# SCH_HC_Business_Card_2023-06-01.net
KiCad netlist of a schematic drawn in EasyEDA
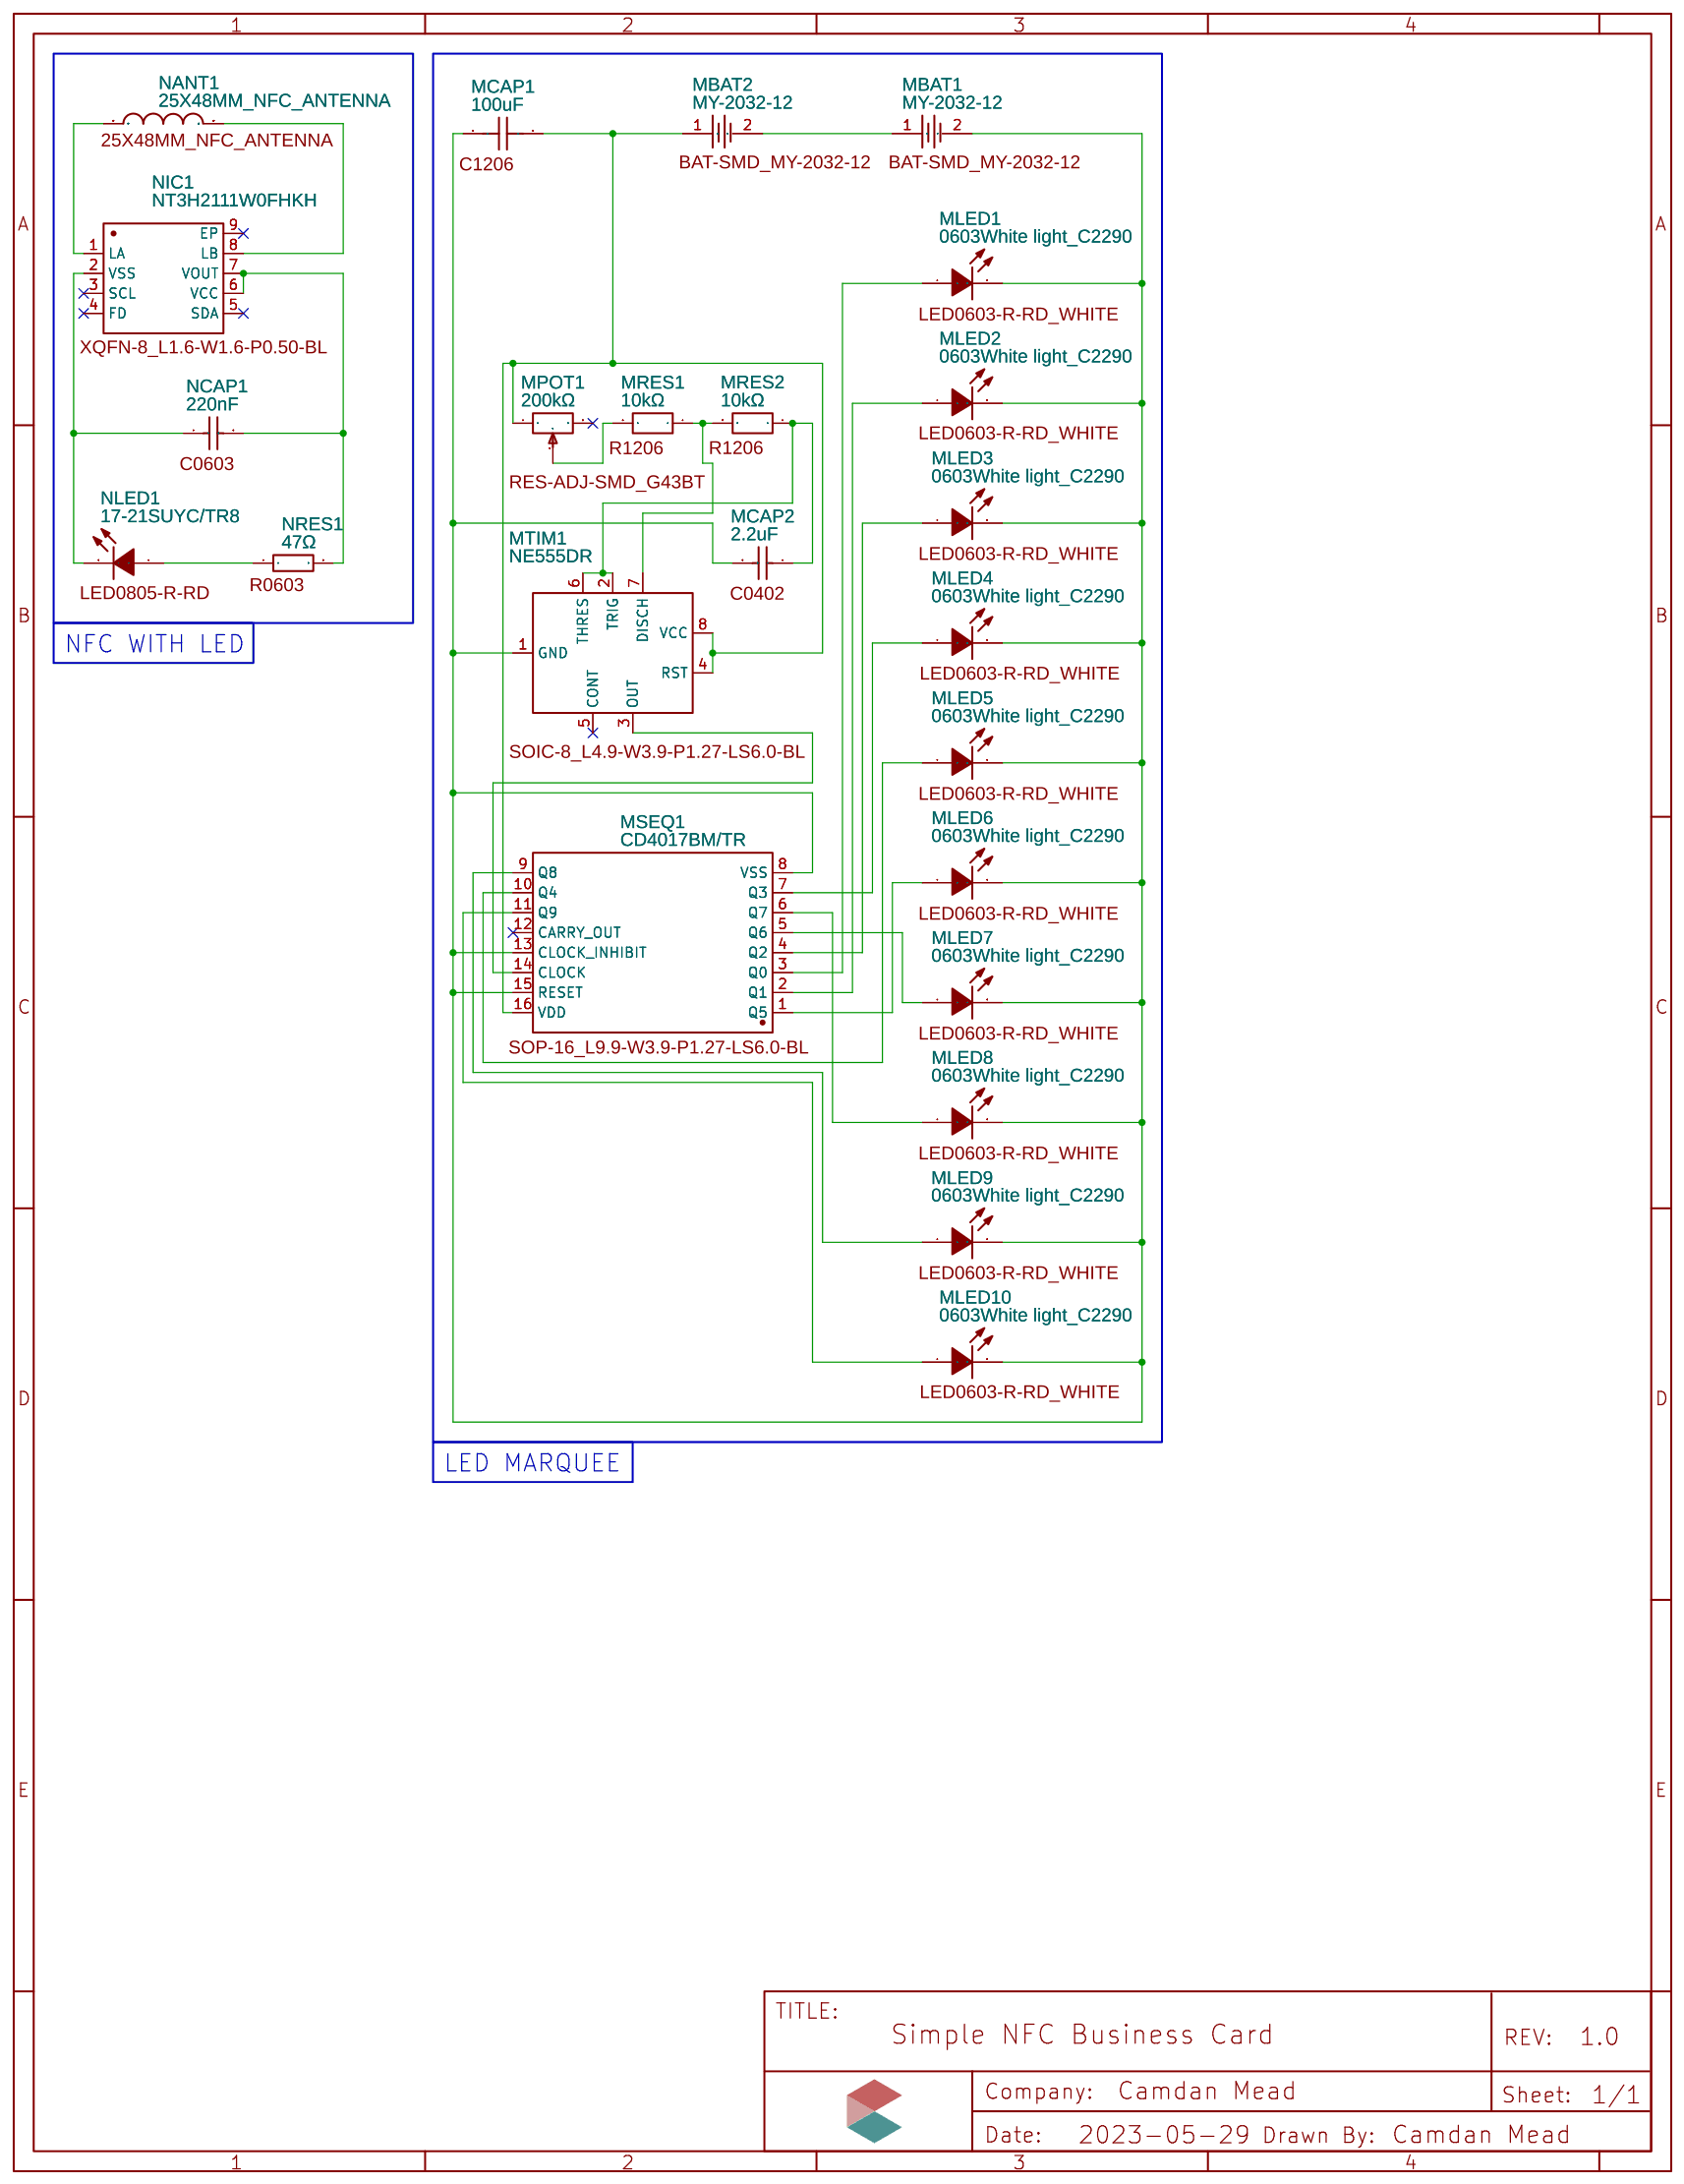
[diagram p0: schematic sheet]

(export (version "E")
  (design (tool "Eeschema 10.0.6"))
  (components
    (comp (ref "MBAT1")
      (value "MY-2032-12")
      (fields (field (name "BOM_Supplier Part") "C964833"))
      (libsource (lib "") (part "MY-2032-12"))
    )
    (comp (ref "MBAT2")
      (value "MY-2032-12")
      (fields (field (name "BOM_Supplier Part") "C964833"))
      (libsource (lib "") (part "MY-2032-12"))
    )
    (comp (ref "MCAP1")
      (value "100uF")
      (fields
        (field (name "BOM_Manufacturer Part") "JMK316ABJ107ML-T")
        (field (name "BOM_Supplier Part") "C268006")
      )
      (libsource (lib "") (part "JMK316ABJ107ML-T"))
    )
    (comp (ref "MCAP2")
      (value "2.2uF")
      (fields
        (field (name "BOM_Manufacturer Part") "GRM155R60J225ME15D")
        (field (name "BOM_Supplier Part") "C76993")
      )
      (libsource (lib "") (part "GRM155R60J225ME15D"))
    )
    (comp (ref "MLED1")
      (value "0603White light_C2290")
      (fields (field (name "BOM_Manufacturer Part") "KT-0603白灯") (field (name "BOM_Supplier Part") "C2290"))
      (libsource (lib "") (part "0603White light_C2290_1"))
    )
    (comp (ref "MLED2")
      (value "0603White light_C2290")
      (fields (field (name "BOM_Manufacturer Part") "KT-0603白灯") (field (name "BOM_Supplier Part") "C2290"))
      (libsource (lib "") (part "0603White light_C2290"))
    )
    (comp (ref "MLED3")
      (value "0603White light_C2290")
      (fields (field (name "BOM_Manufacturer Part") "KT-0603白灯") (field (name "BOM_Supplier Part") "C2290"))
      (libsource (lib "") (part "0603White light_C2290_4"))
    )
    (comp (ref "MLED4")
      (value "0603White light_C2290")
      (fields (field (name "BOM_Manufacturer Part") "KT-0603白灯") (field (name "BOM_Supplier Part") "C2290"))
      (libsource (lib "") (part "0603White light_C2290_2"))
    )
    (comp (ref "MLED5")
      (value "0603White light_C2290")
      (fields (field (name "BOM_Manufacturer Part") "KT-0603白灯") (field (name "BOM_Supplier Part") "C2290"))
      (libsource (lib "") (part "0603White light_C2290_1"))
    )
    (comp (ref "MLED6")
      (value "0603White light_C2290")
      (fields (field (name "BOM_Manufacturer Part") "KT-0603白灯") (field (name "BOM_Supplier Part") "C2290"))
      (libsource (lib "") (part "0603White light_C2290_1"))
    )
    (comp (ref "MLED7")
      (value "0603White light_C2290")
      (fields (field (name "BOM_Manufacturer Part") "KT-0603白灯") (field (name "BOM_Supplier Part") "C2290"))
      (libsource (lib "") (part "0603White light_C2290_1"))
    )
    (comp (ref "MLED8")
      (value "0603White light_C2290")
      (fields (field (name "BOM_Manufacturer Part") "KT-0603白灯") (field (name "BOM_Supplier Part") "C2290"))
      (libsource (lib "") (part "0603White light_C2290_1"))
    )
    (comp (ref "MLED9")
      (value "0603White light_C2290")
      (fields (field (name "BOM_Manufacturer Part") "KT-0603白灯") (field (name "BOM_Supplier Part") "C2290"))
      (libsource (lib "") (part "0603White light_C2290_4"))
    )
    (comp (ref "MLED10")
      (value "0603White light_C2290")
      (fields (field (name "BOM_Manufacturer Part") "KT-0603白灯") (field (name "BOM_Supplier Part") "C2290"))
      (libsource (lib "") (part "0603White light_C2290_3"))
    )
    (comp (ref "MPOT1")
      (value "200kΩ")
      (fields
        (field (name "BOM_Manufacturer Part") "G43BT-B204")
        (field (name "BOM_Supplier Part") "C128150")
      )
      (libsource (lib "") (part "G43BT-B204"))
    )
    (comp (ref "MRES1")
      (value "10kΩ")
      (fields
        (field (name "BOM_Manufacturer Part") "CR1206J10K0P05Z")
        (field (name "BOM_Supplier Part") "C881379")
      )
      (libsource (lib "") (part "CR1206J10K0P05Z_1"))
    )
    (comp (ref "MRES2")
      (value "10kΩ")
      (fields
        (field (name "BOM_Manufacturer Part") "CR1206J10K0P05Z")
        (field (name "BOM_Supplier Part") "C881379")
      )
      (libsource (lib "") (part "CR1206J10K0P05Z"))
    )
    (comp (ref "MSEQ1")
      (value "CD4017BM/TR")
      (fields (field (name "BOM_Supplier Part") "C356694"))
      (libsource (lib "") (part "CD4017BM/TR"))
    )
    (comp (ref "MTIM1")
      (value "NE555DR")
      (fields (field (name "BOM_Supplier Part") "C7593"))
      (libsource (lib "") (part "NE555DR"))
    )
    (comp (ref "NANT1") (value "25X48MM_NFC_ANTENNA") (libsource (lib "") (part "25X48MM_NFC_ANTENNA")))
    (comp (ref "NCAP1")
      (value "220nF")
      (fields
        (field (name "BOM_Manufacturer Part") "CL10B224KA8NNNC")
        (field (name "BOM_Supplier Part") "C21120")
      )
      (libsource (lib "") (part "CL10B224KA8NNNC"))
    )
    (comp (ref "NIC1")
      (value "NT3H2111W0FHKH")
      (fields (field (name "BOM_Supplier Part") "C710403"))
      (libsource (lib "") (part "NT3H2111W0FHKH"))
    )
    (comp (ref "NLED1")
      (value "17-21SUYC/TR8")
      (fields (field (name "BOM_Manufacturer Part") "KT-0805黄灯") (field (name "BOM_Supplier Part") "C2296"))
      (libsource (lib "") (part "17-21SUYC/TR8"))
    )
    (comp (ref "NRES1")
      (value "47Ω")
      (fields
        (field (name "BOM_Manufacturer Part") "0603WAF470JT5E")
        (field (name "BOM_Supplier Part") "C23182")
      )
      (libsource (lib "") (part "0603WAF470JT5E"))
    )
  )
  (nets
    (net (code "1") (name "Net-(MBAT1-Pad1)") (class "Default")
      (node (ref "MBAT1") (pin "1") (pinfunction "1_1") (pintype "input"))
      (node (ref "MBAT2") (pin "2") (pinfunction "2_2") (pintype "input"))
    )
    (net (code "2") (name "Net-(MLED1-A)") (class "Default")
      (node (ref "MLED1") (pin "1") (pinfunction "A_1") (pintype "unspecified"))
      (node (ref "MSEQ1") (pin "3") (pinfunction "Q0_3") (pintype "unspecified"))
    )
    (net (code "3") (name "Net-(MLED1-K)") (class "Default")
      (node (ref "MBAT1") (pin "2") (pinfunction "2_2") (pintype "input"))
      (node (ref "MCAP1") (pin "2") (pinfunction "2_2") (pintype "unspecified"))
      (node (ref "MCAP2") (pin "2") (pinfunction "2_2") (pintype "input"))
      (node (ref "MLED1") (pin "2") (pinfunction "K_2") (pintype "unspecified"))
      (node (ref "MLED10") (pin "2") (pinfunction "K_2") (pintype "unspecified"))
      (node (ref "MLED2") (pin "2") (pinfunction "K_2") (pintype "unspecified"))
      (node (ref "MLED3") (pin "2") (pinfunction "K_2") (pintype "unspecified"))
      (node (ref "MLED4") (pin "2") (pinfunction "K_2") (pintype "unspecified"))
      (node (ref "MLED5") (pin "2") (pinfunction "K_2") (pintype "unspecified"))
      (node (ref "MLED6") (pin "2") (pinfunction "K_2") (pintype "unspecified"))
      (node (ref "MLED7") (pin "2") (pinfunction "K_2") (pintype "unspecified"))
      (node (ref "MLED8") (pin "2") (pinfunction "K_2") (pintype "unspecified"))
      (node (ref "MLED9") (pin "2") (pinfunction "K_2") (pintype "unspecified"))
      (node (ref "MSEQ1") (pin "13") (pinfunction "CLOCK_INHIBIT_13") (pintype "unspecified"))
      (node (ref "MSEQ1") (pin "15") (pinfunction "RESET_15") (pintype "unspecified"))
      (node (ref "MSEQ1") (pin "8") (pinfunction "VSS_8") (pintype "unspecified"))
      (node (ref "MTIM1") (pin "1") (pinfunction "GND_1") (pintype "unspecified"))
    )
    (net (code "4") (name "Net-(MLED2-A)") (class "Default")
      (node (ref "MLED2") (pin "1") (pinfunction "A_1") (pintype "unspecified"))
      (node (ref "MSEQ1") (pin "2") (pinfunction "Q1_2") (pintype "unspecified"))
    )
    (net (code "5") (name "Net-(MLED3-A)") (class "Default")
      (node (ref "MLED3") (pin "1") (pinfunction "A_1") (pintype "unspecified"))
      (node (ref "MSEQ1") (pin "4") (pinfunction "Q2_4") (pintype "unspecified"))
    )
    (net (code "6") (name "Net-(MLED4-A)") (class "Default")
      (node (ref "MLED4") (pin "1") (pinfunction "A_1") (pintype "unspecified"))
      (node (ref "MSEQ1") (pin "7") (pinfunction "Q3_7") (pintype "unspecified"))
    )
    (net (code "7") (name "Net-(MLED5-A)") (class "Default")
      (node (ref "MLED5") (pin "1") (pinfunction "A_1") (pintype "unspecified"))
      (node (ref "MSEQ1") (pin "10") (pinfunction "Q4_10") (pintype "unspecified"))
    )
    (net (code "8") (name "Net-(MLED6-A)") (class "Default")
      (node (ref "MLED6") (pin "1") (pinfunction "A_1") (pintype "unspecified"))
      (node (ref "MSEQ1") (pin "1") (pinfunction "Q5_1") (pintype "unspecified"))
    )
    (net (code "9") (name "Net-(MLED7-A)") (class "Default")
      (node (ref "MLED7") (pin "1") (pinfunction "A_1") (pintype "unspecified"))
      (node (ref "MSEQ1") (pin "5") (pinfunction "Q6_5") (pintype "unspecified"))
    )
    (net (code "10") (name "Net-(MLED8-A)") (class "Default")
      (node (ref "MLED8") (pin "1") (pinfunction "A_1") (pintype "unspecified"))
      (node (ref "MSEQ1") (pin "6") (pinfunction "Q7_6") (pintype "unspecified"))
    )
    (net (code "11") (name "Net-(MLED9-A)") (class "Default")
      (node (ref "MLED9") (pin "1") (pinfunction "A_1") (pintype "unspecified"))
      (node (ref "MSEQ1") (pin "9") (pinfunction "Q8_9") (pintype "unspecified"))
    )
    (net (code "12") (name "Net-(MLED10-A)") (class "Default")
      (node (ref "MLED10") (pin "1") (pinfunction "A_1") (pintype "unspecified"))
      (node (ref "MSEQ1") (pin "11") (pinfunction "Q9_11") (pintype "unspecified"))
    )
    (net (code "13") (name "Net-(MPOT1-Pad2)") (class "Default")
      (node (ref "MPOT1") (pin "2") (pinfunction "2_2") (pintype "input"))
      (node (ref "MRES1") (pin "2") (pinfunction "2_2") (pintype "unspecified"))
    )
    (net (code "14") (name "Net-(MSEQ1-CLOCK)") (class "Default")
      (node (ref "MSEQ1") (pin "14") (pinfunction "CLOCK_14") (pintype "unspecified"))
      (node (ref "MTIM1") (pin "3") (pinfunction "OUT_3") (pintype "unspecified"))
    )
    (net (code "15") (name "Net-(MSEQ1-VDD)") (class "Default")
      (node (ref "MBAT2") (pin "1") (pinfunction "1_1") (pintype "input"))
      (node (ref "MCAP1") (pin "1") (pinfunction "1_1") (pintype "unspecified"))
      (node (ref "MPOT1") (pin "1") (pinfunction "1_1") (pintype "input"))
      (node (ref "MSEQ1") (pin "16") (pinfunction "VDD_16") (pintype "unspecified"))
      (node (ref "MTIM1") (pin "4") (pinfunction "RST_4") (pintype "unspecified"))
      (node (ref "MTIM1") (pin "8") (pinfunction "VCC_8") (pintype "unspecified"))
    )
    (net (code "16") (name "Net-(MTIM1-DISCH)") (class "Default")
      (node (ref "MRES1") (pin "1") (pinfunction "1_1") (pintype "unspecified"))
      (node (ref "MRES2") (pin "2") (pinfunction "2_2") (pintype "unspecified"))
      (node (ref "MTIM1") (pin "7") (pinfunction "DISCH_7") (pintype "unspecified"))
    )
    (net (code "17") (name "Net-(MTIM1-THRES)") (class "Default")
      (node (ref "MCAP2") (pin "1") (pinfunction "1_1") (pintype "input"))
      (node (ref "MRES2") (pin "1") (pinfunction "1_1") (pintype "unspecified"))
      (node (ref "MTIM1") (pin "2") (pinfunction "TRIG_2") (pintype "unspecified"))
      (node (ref "MTIM1") (pin "6") (pinfunction "THRES_6") (pintype "unspecified"))
    )
    (net (code "18") (name "Net-(NIC1-LA)") (class "Default")
      (node (ref "NANT1") (pin "P$1") (pinfunction "P$1_P$1") (pintype "bidirectional"))
      (node (ref "NIC1") (pin "1") (pinfunction "LA_1") (pintype "unspecified"))
    )
    (net (code "19") (name "Net-(NIC1-LB)") (class "Default")
      (node (ref "NANT1") (pin "P$2") (pinfunction "P$2_P$2") (pintype "bidirectional"))
      (node (ref "NIC1") (pin "8") (pinfunction "LB_8") (pintype "unspecified"))
    )
    (net (code "20") (name "Net-(NIC1-VCC)") (class "Default")
      (node (ref "NCAP1") (pin "2") (pinfunction "2_2") (pintype "input"))
      (node (ref "NIC1") (pin "6") (pinfunction "VCC_6") (pintype "unspecified"))
      (node (ref "NIC1") (pin "7") (pinfunction "VOUT_7") (pintype "unspecified"))
      (node (ref "NRES1") (pin "2") (pinfunction "2_2") (pintype "input"))
    )
    (net (code "21") (name "Net-(NIC1-VSS)") (class "Default")
      (node (ref "NCAP1") (pin "1") (pinfunction "1_1") (pintype "input"))
      (node (ref "NIC1") (pin "2") (pinfunction "VSS_2") (pintype "unspecified"))
      (node (ref "NLED1") (pin "2") (pinfunction "-_2") (pintype "unspecified"))
    )
    (net (code "22") (name "Net-(NLED1-+)") (class "Default")
      (node (ref "NLED1") (pin "1") (pinfunction "+_1") (pintype "unspecified"))
      (node (ref "NRES1") (pin "1") (pinfunction "1_1") (pintype "input"))
    )
    (net (code "23") (name "unconnected-(MPOT1-Pad3)") (class "Default")
      (node (ref "MPOT1") (pin "3") (pinfunction "3_3") (pintype "input+no_connect"))
    )
    (net (code "24") (name "unconnected-(MSEQ1-CARRY_OUT-Pad12)") (class "Default")
      (node (ref "MSEQ1") (pin "12") (pinfunction "CARRY_OUT_12") (pintype "unspecified+no_connect"))
    )
    (net (code "25") (name "unconnected-(MTIM1-CONT-Pad5)") (class "Default")
      (node (ref "MTIM1") (pin "5") (pinfunction "CONT_5") (pintype "unspecified+no_connect"))
    )
    (net (code "26") (name "unconnected-(NIC1-EP-Pad9)") (class "Default")
      (node (ref "NIC1") (pin "9") (pinfunction "EP_9") (pintype "unspecified+no_connect"))
    )
    (net (code "27") (name "unconnected-(NIC1-FD-Pad4)") (class "Default")
      (node (ref "NIC1") (pin "4") (pinfunction "FD_4") (pintype "unspecified+no_connect"))
    )
    (net (code "28") (name "unconnected-(NIC1-SCL-Pad3)") (class "Default")
      (node (ref "NIC1") (pin "3") (pinfunction "SCL_3") (pintype "unspecified+no_connect"))
    )
    (net (code "29") (name "unconnected-(NIC1-SDA-Pad5)") (class "Default")
      (node (ref "NIC1") (pin "5") (pinfunction "SDA_5") (pintype "unspecified+no_connect"))
    )
  )
)
